# schematic.net
KiCad netlist of a schematic drawn in EasyEDA
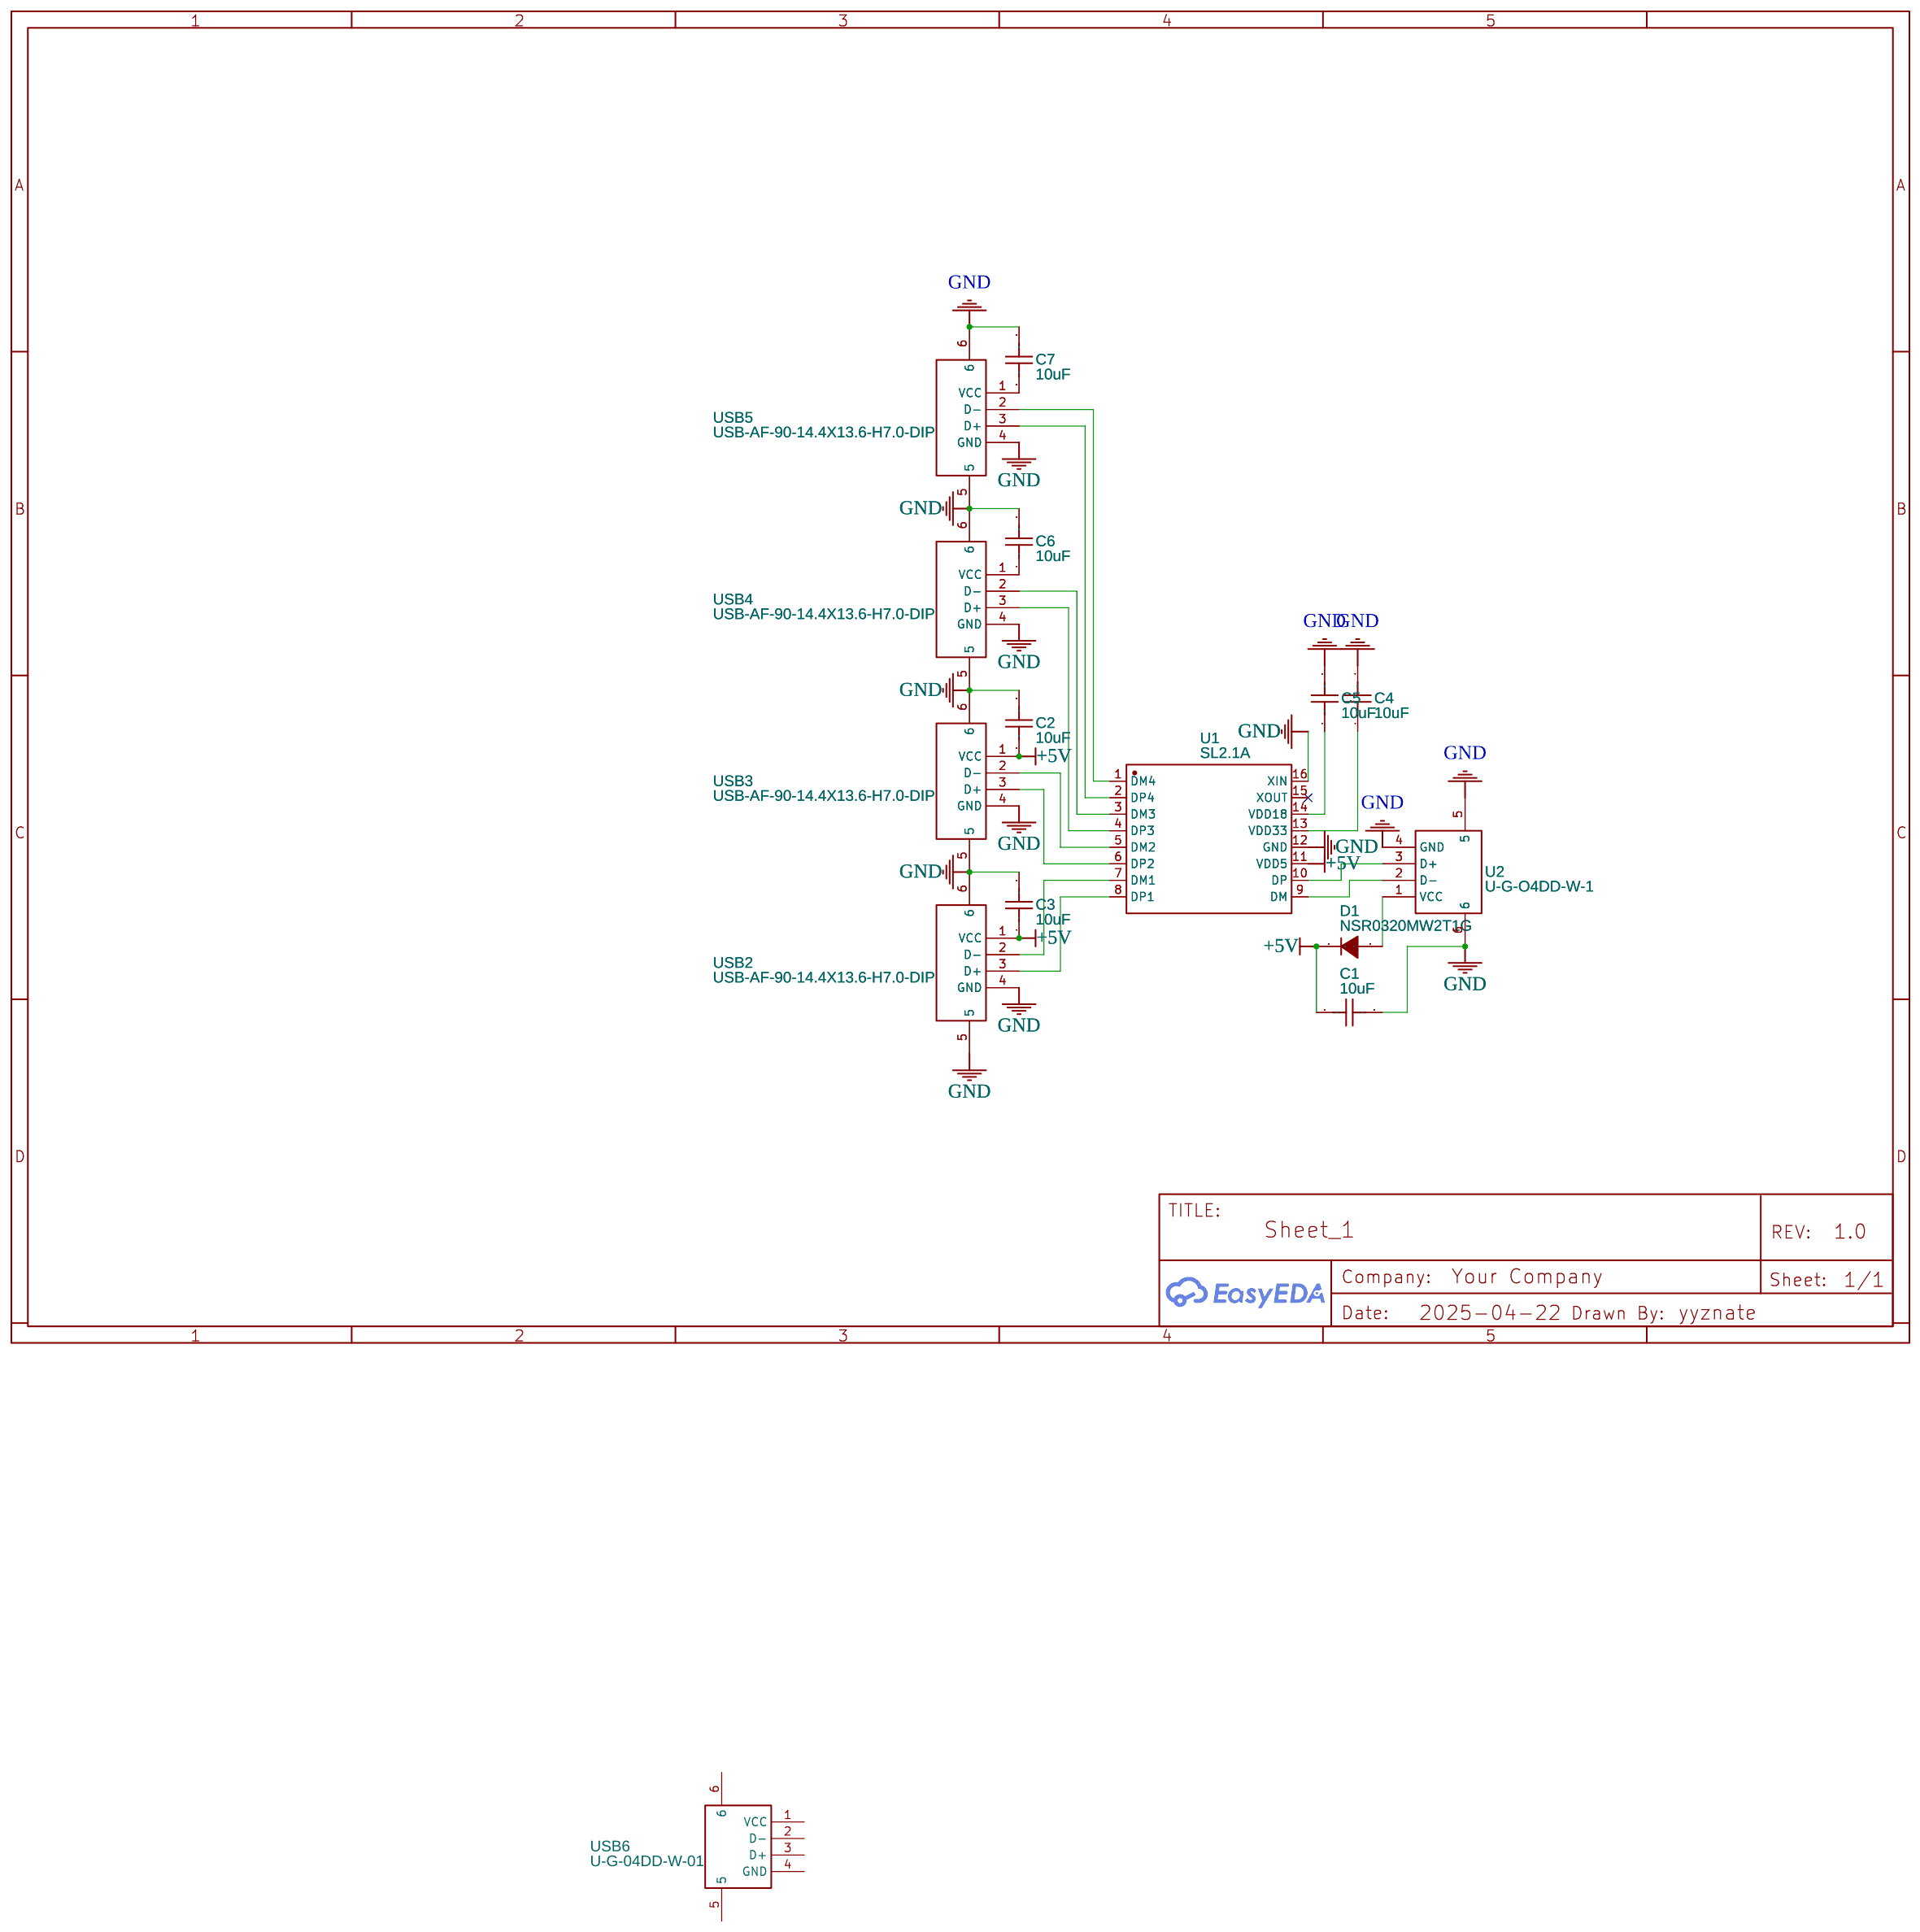
[diagram p0: schematic sheet]

(export (version "E")
  (design (tool "Eeschema 10.0.6"))
  (components
    (comp (ref "C1")
      (value "10uF")
      (fields
        (field (name "Manufacturer Part") "CL10A106KP8NNNC")
        (field (name "Manufacturer") "SAMSUNG(三星)")
      )
      (libsource (lib "") (part "CL10A106KP8NNNC_1"))
    )
    (comp (ref "C2")
      (value "10uF")
      (fields
        (field (name "Manufacturer Part") "CL10A106KP8NNNC")
        (field (name "Manufacturer") "SAMSUNG(三星)")
      )
      (libsource (lib "") (part "CL10A106KP8NNNC"))
    )
    (comp (ref "C3")
      (value "10uF")
      (fields
        (field (name "Manufacturer Part") "CL10A106KP8NNNC")
        (field (name "Manufacturer") "SAMSUNG(三星)")
      )
      (libsource (lib "") (part "CL10A106KP8NNNC"))
    )
    (comp (ref "C4")
      (value "10uF")
      (fields
        (field (name "Manufacturer Part") "CL10A106KP8NNNC")
        (field (name "Manufacturer") "SAMSUNG(三星)")
      )
      (libsource (lib "") (part "CL10A106KP8NNNC"))
    )
    (comp (ref "C5")
      (value "10uF")
      (fields
        (field (name "Manufacturer Part") "CL10A106KP8NNNC")
        (field (name "Manufacturer") "SAMSUNG(三星)")
      )
      (libsource (lib "") (part "CL10A106KP8NNNC"))
    )
    (comp (ref "C6")
      (value "10uF")
      (fields
        (field (name "Manufacturer Part") "CL10A106KP8NNNC")
        (field (name "Manufacturer") "SAMSUNG(三星)")
      )
      (libsource (lib "") (part "CL10A106KP8NNNC"))
    )
    (comp (ref "C7")
      (value "10uF")
      (fields
        (field (name "Manufacturer Part") "CL10A106KP8NNNC")
        (field (name "Manufacturer") "SAMSUNG(三星)")
      )
      (libsource (lib "") (part "CL10A106KP8NNNC"))
    )
    (comp (ref "D1")
      (value "NSR0320MW2T1G")
      (fields (field (name "Manufacturer") "onsemi(安森美)"))
      (libsource (lib "") (part "NSR0320MW2T1G"))
    )
    (comp (ref "U1")
      (value "SL2.1A")
      (fields (field (name "Manufacturer") "CoreChips(和芯润德)"))
      (libsource (lib "") (part "SL2.1A"))
    )
    (comp (ref "U2")
      (value "U-G-O4DD-W-1")
      (fields (field (name "Manufacturer") "韩国韩荣"))
      (libsource (lib "") (part "U-G-O4DD-W-1"))
    )
    (comp (ref "USB2")
      (value "USB-AF-90-14.4X13.6-H7.0-DIP")
      (fields (field (name "Manufacturer Part") "903-131A1011D10100") (field (name "Manufacturer") "精拓金"))
      (libsource (lib "") (part "USB-AF-90-14.4X13.6-H7.0-DIP"))
    )
    (comp (ref "USB3")
      (value "USB-AF-90-14.4X13.6-H7.0-DIP")
      (fields (field (name "Manufacturer Part") "903-131A1011D10100") (field (name "Manufacturer") "精拓金"))
      (libsource (lib "") (part "USB-AF-90-14.4X13.6-H7.0-DIP"))
    )
    (comp (ref "USB4")
      (value "USB-AF-90-14.4X13.6-H7.0-DIP")
      (fields (field (name "Manufacturer Part") "903-131A1011D10100") (field (name "Manufacturer") "精拓金"))
      (libsource (lib "") (part "USB-AF-90-14.4X13.6-H7.0-DIP"))
    )
    (comp (ref "USB5")
      (value "USB-AF-90-14.4X13.6-H7.0-DIP")
      (fields (field (name "Manufacturer Part") "903-131A1011D10100") (field (name "Manufacturer") "精拓金"))
      (libsource (lib "") (part "USB-AF-90-14.4X13.6-H7.0-DIP"))
    )
    (comp (ref "USB6")
      (value "U-G-04DD-W-01")
      (fields (field (name "Manufacturer Part") "U-G-O4DD-W-1") (field (name "Manufacturer") "韩国韩荣"))
      (libsource (lib "") (part "U-G-04DD-W-01"))
    )
  )
  (nets
    (net (code "1") (name "+5V") (class "Default")
      (node (ref "C1") (pin "1") (pinfunction "1_1") (pintype "unspecified"))
      (node (ref "C2") (pin "1") (pinfunction "1_1") (pintype "unspecified"))
      (node (ref "C3") (pin "1") (pinfunction "1_1") (pintype "unspecified"))
      (node (ref "D1") (pin "1") (pinfunction "C_1") (pintype "unspecified"))
      (node (ref "U1") (pin "11") (pinfunction "VDD5_11") (pintype "unspecified"))
      (node (ref "USB2") (pin "1") (pinfunction "VCC_1") (pintype "unspecified"))
      (node (ref "USB3") (pin "1") (pinfunction "VCC_1") (pintype "unspecified"))
    )
    (net (code "2") (name "GND") (class "Default")
      (node (ref "C1") (pin "2") (pinfunction "2_2") (pintype "unspecified"))
      (node (ref "C2") (pin "2") (pinfunction "2_2") (pintype "unspecified"))
      (node (ref "C3") (pin "2") (pinfunction "2_2") (pintype "unspecified"))
      (node (ref "C4") (pin "2") (pinfunction "2_2") (pintype "unspecified"))
      (node (ref "C5") (pin "2") (pinfunction "2_2") (pintype "unspecified"))
      (node (ref "C6") (pin "2") (pinfunction "2_2") (pintype "unspecified"))
      (node (ref "C7") (pin "2") (pinfunction "2_2") (pintype "unspecified"))
      (node (ref "U1") (pin "12") (pinfunction "GND_12") (pintype "unspecified"))
      (node (ref "U1") (pin "16") (pinfunction "XIN_16") (pintype "unspecified"))
      (node (ref "U2") (pin "4") (pinfunction "GND_4") (pintype "unspecified"))
      (node (ref "U2") (pin "5") (pinfunction "5_5") (pintype "unspecified"))
      (node (ref "U2") (pin "6") (pinfunction "6_6") (pintype "unspecified"))
      (node (ref "USB2") (pin "4") (pinfunction "GND_4") (pintype "unspecified"))
      (node (ref "USB2") (pin "5") (pinfunction "5_5") (pintype "unspecified"))
      (node (ref "USB2") (pin "6") (pinfunction "6_6") (pintype "unspecified"))
      (node (ref "USB3") (pin "4") (pinfunction "GND_4") (pintype "unspecified"))
      (node (ref "USB3") (pin "5") (pinfunction "5_5") (pintype "unspecified"))
      (node (ref "USB3") (pin "6") (pinfunction "6_6") (pintype "unspecified"))
      (node (ref "USB4") (pin "4") (pinfunction "GND_4") (pintype "unspecified"))
      (node (ref "USB4") (pin "5") (pinfunction "5_5") (pintype "unspecified"))
      (node (ref "USB4") (pin "6") (pinfunction "6_6") (pintype "unspecified"))
      (node (ref "USB5") (pin "4") (pinfunction "GND_4") (pintype "unspecified"))
      (node (ref "USB5") (pin "5") (pinfunction "5_5") (pintype "unspecified"))
      (node (ref "USB5") (pin "6") (pinfunction "6_6") (pintype "unspecified"))
    )
    (net (code "3") (name "Net-(D1-A)") (class "Default")
      (node (ref "D1") (pin "2") (pinfunction "A_2") (pintype "unspecified"))
      (node (ref "U2") (pin "1") (pinfunction "VCC_1") (pintype "unspecified"))
    )
    (net (code "4") (name "Net-(U1-DM)") (class "Default")
      (node (ref "U1") (pin "9") (pinfunction "DM_9") (pintype "unspecified"))
      (node (ref "U2") (pin "2") (pinfunction "D-_2") (pintype "unspecified"))
    )
    (net (code "5") (name "Net-(U1-DM1)") (class "Default")
      (node (ref "U1") (pin "7") (pinfunction "DM1_7") (pintype "unspecified"))
      (node (ref "USB2") (pin "2") (pinfunction "D-_2") (pintype "unspecified"))
    )
    (net (code "6") (name "Net-(U1-DM2)") (class "Default")
      (node (ref "U1") (pin "5") (pinfunction "DM2_5") (pintype "unspecified"))
      (node (ref "USB3") (pin "2") (pinfunction "D-_2") (pintype "unspecified"))
    )
    (net (code "7") (name "Net-(U1-DM3)") (class "Default")
      (node (ref "U1") (pin "3") (pinfunction "DM3_3") (pintype "unspecified"))
      (node (ref "USB4") (pin "2") (pinfunction "D-_2") (pintype "unspecified"))
    )
    (net (code "8") (name "Net-(U1-DM4)") (class "Default")
      (node (ref "U1") (pin "1") (pinfunction "DM4_1") (pintype "unspecified"))
      (node (ref "USB5") (pin "2") (pinfunction "D-_2") (pintype "unspecified"))
    )
    (net (code "9") (name "Net-(U1-DP)") (class "Default")
      (node (ref "U1") (pin "10") (pinfunction "DP_10") (pintype "unspecified"))
      (node (ref "U2") (pin "3") (pinfunction "D+_3") (pintype "unspecified"))
    )
    (net (code "10") (name "Net-(U1-DP1)") (class "Default")
      (node (ref "U1") (pin "8") (pinfunction "DP1_8") (pintype "unspecified"))
      (node (ref "USB2") (pin "3") (pinfunction "D+_3") (pintype "unspecified"))
    )
    (net (code "11") (name "Net-(U1-DP2)") (class "Default")
      (node (ref "U1") (pin "6") (pinfunction "DP2_6") (pintype "unspecified"))
      (node (ref "USB3") (pin "3") (pinfunction "D+_3") (pintype "unspecified"))
    )
    (net (code "12") (name "Net-(U1-DP3)") (class "Default")
      (node (ref "U1") (pin "4") (pinfunction "DP3_4") (pintype "unspecified"))
      (node (ref "USB4") (pin "3") (pinfunction "D+_3") (pintype "unspecified"))
    )
    (net (code "13") (name "Net-(U1-DP4)") (class "Default")
      (node (ref "U1") (pin "2") (pinfunction "DP4_2") (pintype "unspecified"))
      (node (ref "USB5") (pin "3") (pinfunction "D+_3") (pintype "unspecified"))
    )
    (net (code "14") (name "Net-(U1-VDD18)") (class "Default")
      (node (ref "C5") (pin "1") (pinfunction "1_1") (pintype "unspecified"))
      (node (ref "U1") (pin "14") (pinfunction "VDD18_14") (pintype "unspecified"))
    )
    (net (code "15") (name "Net-(U1-VDD33)") (class "Default")
      (node (ref "C4") (pin "1") (pinfunction "1_1") (pintype "unspecified"))
      (node (ref "U1") (pin "13") (pinfunction "VDD33_13") (pintype "unspecified"))
    )
    (net (code "16") (name "Net-(USB4-VCC)") (class "Default")
      (node (ref "C6") (pin "1") (pinfunction "1_1") (pintype "unspecified"))
      (node (ref "USB4") (pin "1") (pinfunction "VCC_1") (pintype "unspecified"))
    )
    (net (code "17") (name "Net-(USB5-VCC)") (class "Default")
      (node (ref "C7") (pin "1") (pinfunction "1_1") (pintype "unspecified"))
      (node (ref "USB5") (pin "1") (pinfunction "VCC_1") (pintype "unspecified"))
    )
    (net (code "18") (name "unconnected-(U1-XOUT-Pad15)") (class "Default")
      (node (ref "U1") (pin "15") (pinfunction "XOUT_15") (pintype "unspecified+no_connect"))
    )
    (net (code "19") (name "unconnected-(USB6-D+-Pad3)") (class "Default")
      (node (ref "USB6") (pin "3") (pinfunction "D+_3") (pintype "unspecified"))
    )
    (net (code "20") (name "unconnected-(USB6-D--Pad2)") (class "Default")
      (node (ref "USB6") (pin "2") (pinfunction "D-_2") (pintype "unspecified"))
    )
    (net (code "21") (name "unconnected-(USB6-GND-Pad4)") (class "Default")
      (node (ref "USB6") (pin "4") (pinfunction "GND_4") (pintype "unspecified"))
    )
    (net (code "22") (name "unconnected-(USB6-Pad5)") (class "Default")
      (node (ref "USB6") (pin "5") (pinfunction "5_5") (pintype "unspecified"))
    )
    (net (code "23") (name "unconnected-(USB6-Pad6)") (class "Default")
      (node (ref "USB6") (pin "6") (pinfunction "6_6") (pintype "unspecified"))
    )
    (net (code "24") (name "unconnected-(USB6-VCC-Pad1)") (class "Default")
      (node (ref "USB6") (pin "1") (pinfunction "VCC_1") (pintype "unspecified"))
    )
  )
)
